# thermostat.net
KiCad netlist of a schematic drawn in EAGLE
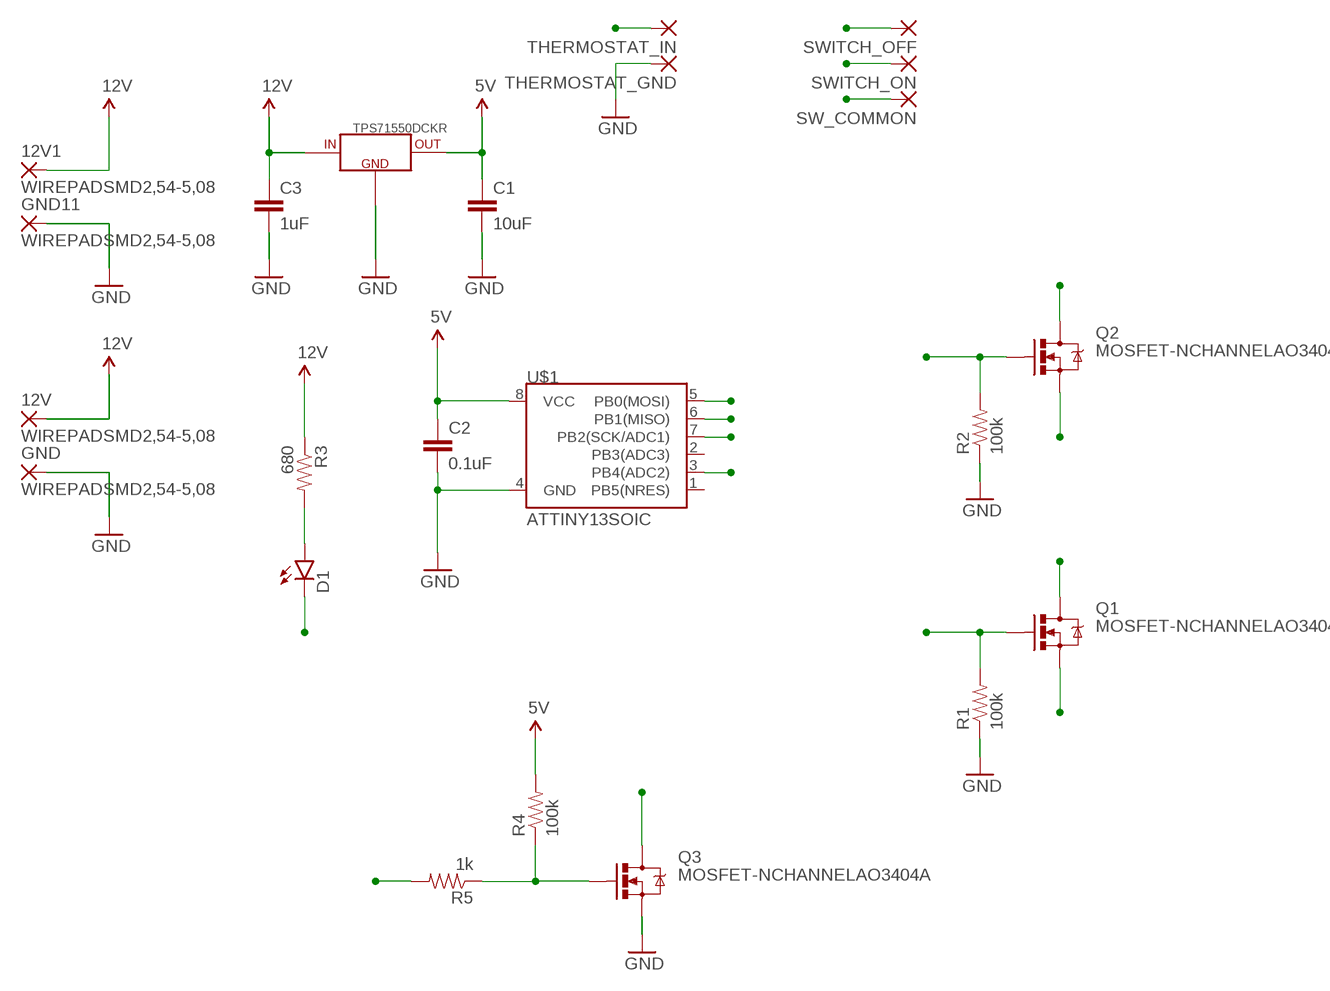
[diagram p0: schematic, sheet 1]

(export (version "E")
  (design (tool "Eeschema 10.0.6"))
  (components
    (comp (ref "12V")
      (value "WIREPADSMD2,54-5,08")
      (footprint "eagle-import:SMD2,54-5,08")
      (libsource (lib "eagle-import") (part "WIREPADSMD2,54-5,08"))
    )
    (comp (ref "12V1")
      (value "WIREPADSMD2,54-5,08")
      (footprint "eagle-import:SMD2,54-5,08")
      (libsource (lib "eagle-import") (part "WIREPADSMD2,54-5,08"))
    )
    (comp (ref "C1")
      (value "10uF")
      (footprint "eagle-import:1210")
      (libsource (lib "eagle-import") (part "CAP1210"))
    )
    (comp (ref "C2")
      (value "0.1uF")
      (footprint "eagle-import:0805")
      (libsource (lib "eagle-import") (part "CAP0805"))
    )
    (comp (ref "C3")
      (value "1uF")
      (footprint "eagle-import:1210")
      (libsource (lib "eagle-import") (part "CAP1210"))
    )
    (comp (ref "D1")
      (value "LED0603")
      (footprint "eagle-import:LED-0603")
      (libsource (lib "eagle-import") (part "LED0603"))
    )
    (comp (ref "GND")
      (value "WIREPADSMD2,54-5,08")
      (footprint "eagle-import:SMD2,54-5,08")
      (libsource (lib "eagle-import") (part "WIREPADSMD2,54-5,08"))
    )
    (comp (ref "GND11")
      (value "WIREPADSMD2,54-5,08")
      (footprint "eagle-import:SMD2,54-5,08")
      (libsource (lib "eagle-import") (part "WIREPADSMD2,54-5,08"))
    )
    (comp (ref "Q1")
      (value "MOSFET-NCHANNELAO3404A")
      (footprint "eagle-import:SOT23-3")
      (libsource (lib "eagle-import") (part "MOSFET-NCHANNELAO3404A"))
    )
    (comp (ref "Q2")
      (value "MOSFET-NCHANNELAO3404A")
      (footprint "eagle-import:SOT23-3")
      (libsource (lib "eagle-import") (part "MOSFET-NCHANNELAO3404A"))
    )
    (comp (ref "Q3")
      (value "MOSFET-NCHANNELAO3404A")
      (footprint "eagle-import:SOT23-3")
      (libsource (lib "eagle-import") (part "MOSFET-NCHANNELAO3404A"))
    )
    (comp (ref "R1")
      (value "100k")
      (footprint "eagle-import:0805")
      (libsource (lib "eagle-import") (part "RESISTOR0805-RES"))
    )
    (comp (ref "R2")
      (value "100k")
      (footprint "eagle-import:0805")
      (libsource (lib "eagle-import") (part "RESISTOR0805-RES"))
    )
    (comp (ref "R3")
      (value "680")
      (footprint "eagle-import:0805")
      (libsource (lib "eagle-import") (part "RESISTOR0805-RES"))
    )
    (comp (ref "R4")
      (value "100k")
      (footprint "eagle-import:0805")
      (libsource (lib "eagle-import") (part "RESISTOR0805-RES"))
    )
    (comp (ref "R5")
      (value "1k")
      (footprint "eagle-import:0805")
      (libsource (lib "eagle-import") (part "RESISTOR0805-RES"))
    )
    (comp (ref "SWITCH_OFF")
      (value "WIREPADSMD2,54-5,08")
      (footprint "eagle-import:SMD2,54-5,08")
      (libsource (lib "eagle-import") (part "WIREPADSMD2,54-5,08"))
    )
    (comp (ref "SWITCH_ON")
      (value "WIREPADSMD2,54-5,08")
      (footprint "eagle-import:SMD2,54-5,08")
      (libsource (lib "eagle-import") (part "WIREPADSMD2,54-5,08"))
    )
    (comp (ref "SW_COMMON")
      (value "WIREPADSMD2,54-5,08")
      (footprint "eagle-import:SMD2,54-5,08")
      (libsource (lib "eagle-import") (part "WIREPADSMD2,54-5,08"))
    )
    (comp (ref "THERMOSTAT_GND")
      (value "WIREPADSMD2,54-5,08")
      (footprint "eagle-import:SMD2,54-5,08")
      (libsource (lib "eagle-import") (part "WIREPADSMD2,54-5,08"))
    )
    (comp (ref "THERMOSTAT_IN")
      (value "WIREPADSMD2,54-5,08")
      (footprint "eagle-import:SMD2,54-5,08")
      (libsource (lib "eagle-import") (part "WIREPADSMD2,54-5,08"))
    )
    (comp (ref "TPS71550DCKR")
      (value "TPS715XX")
      (footprint "eagle-import:SC70-5")
      (libsource (lib "eagle-import") (part "TPS715XX"))
    )
    (comp (ref "U$1")
      (value "ATTINY13SOIC")
      (footprint "eagle-import:SO08")
      (libsource (lib "eagle-import") (part "ATTINY13SOIC"))
    )
  )
  (nets
    (net (code "1") (name "/HEAT_OFF") (class "Default")
      (node (ref "Q2") (pin "1") (pinfunction "G_1") (pintype "passive"))
      (node (ref "R2") (pin "2") (pinfunction "2_2") (pintype "passive"))
      (node (ref "U$1") (pin "5") (pinfunction "PB0(MOSI)_5") (pintype "bidirectional"))
    )
    (net (code "2") (name "/HEAT_ON") (class "Default")
      (node (ref "Q1") (pin "1") (pinfunction "G_1") (pintype "passive"))
      (node (ref "R1") (pin "2") (pinfunction "2_2") (pintype "passive"))
      (node (ref "U$1") (pin "6") (pinfunction "PB1(MISO)_6") (pintype "bidirectional"))
    )
    (net (code "3") (name "/LED") (class "Default")
      (node (ref "D1") (pin "C") (pinfunction "C_C") (pintype "passive"))
      (node (ref "U$1") (pin "3") (pinfunction "PB4(ADC2)_3") (pintype "bidirectional"))
    )
    (net (code "4") (name "/SENSOR_IN") (class "Default")
      (node (ref "Q3") (pin "3") (pinfunction "D_3") (pintype "passive"))
      (node (ref "U$1") (pin "7") (pinfunction "PB2(SCK/ADC1)_7") (pintype "bidirectional"))
    )
    (net (code "5") (name "/SWITCH_OFF") (class "Default")
      (node (ref "Q2") (pin "2") (pinfunction "S_2") (pintype "passive"))
      (node (ref "SWITCH_OFF") (pin "1") (pinfunction "P_1") (pintype "passive"))
    )
    (net (code "6") (name "/SWITCH_ON") (class "Default")
      (node (ref "Q1") (pin "2") (pinfunction "S_2") (pintype "passive"))
      (node (ref "SWITCH_ON") (pin "1") (pinfunction "P_1") (pintype "passive"))
    )
    (net (code "7") (name "/SW_COMMON") (class "Default")
      (node (ref "Q1") (pin "3") (pinfunction "D_3") (pintype "passive"))
      (node (ref "Q2") (pin "3") (pinfunction "D_3") (pintype "passive"))
      (node (ref "SW_COMMON") (pin "1") (pinfunction "P_1") (pintype "passive"))
    )
    (net (code "8") (name "/THERMOSTAT_IN") (class "Default")
      (node (ref "R5") (pin "2") (pinfunction "2_2") (pintype "passive"))
      (node (ref "THERMOSTAT_IN") (pin "1") (pinfunction "P_1") (pintype "passive"))
    )
    (net (code "9") (name "5V") (class "Default")
      (node (ref "C1") (pin "1") (pinfunction "1_1") (pintype "passive"))
      (node (ref "C2") (pin "1") (pinfunction "1_1") (pintype "passive"))
      (node (ref "R4") (pin "2") (pinfunction "2_2") (pintype "passive"))
      (node (ref "TPS71550DCKR") (pin "5") (pinfunction "OUT_5") (pintype "bidirectional"))
      (node (ref "U$1") (pin "8") (pinfunction "VCC_8") (pintype "bidirectional"))
    )
    (net (code "10") (name "12V") (class "Default")
      (node (ref "12V") (pin "1") (pinfunction "P_1") (pintype "passive"))
      (node (ref "12V1") (pin "1") (pinfunction "P_1") (pintype "passive"))
      (node (ref "C3") (pin "1") (pinfunction "1_1") (pintype "passive"))
      (node (ref "R3") (pin "1") (pinfunction "1_1") (pintype "passive"))
      (node (ref "TPS71550DCKR") (pin "4") (pinfunction "IN_4") (pintype "bidirectional"))
    )
    (net (code "11") (name "GND") (class "Default")
      (node (ref "C1") (pin "2") (pinfunction "2_2") (pintype "passive"))
      (node (ref "C2") (pin "2") (pinfunction "2_2") (pintype "passive"))
      (node (ref "C3") (pin "2") (pinfunction "2_2") (pintype "passive"))
      (node (ref "GND") (pin "1") (pinfunction "P_1") (pintype "passive"))
      (node (ref "GND11") (pin "1") (pinfunction "P_1") (pintype "passive"))
      (node (ref "Q3") (pin "2") (pinfunction "S_2") (pintype "passive"))
      (node (ref "R1") (pin "1") (pinfunction "1_1") (pintype "passive"))
      (node (ref "R2") (pin "1") (pinfunction "1_1") (pintype "passive"))
      (node (ref "THERMOSTAT_GND") (pin "1") (pinfunction "P_1") (pintype "passive"))
      (node (ref "TPS71550DCKR") (pin "2") (pinfunction "GND_2") (pintype "bidirectional"))
      (node (ref "U$1") (pin "4") (pinfunction "GND_4") (pintype "bidirectional"))
    )
    (net (code "12") (name "Net-(D1-PadA)") (class "Default")
      (node (ref "D1") (pin "A") (pinfunction "A_A") (pintype "passive"))
      (node (ref "R3") (pin "2") (pinfunction "2_2") (pintype "passive"))
    )
    (net (code "13") (name "Net-(Q3-G)") (class "Default")
      (node (ref "Q3") (pin "1") (pinfunction "G_1") (pintype "passive"))
      (node (ref "R4") (pin "1") (pinfunction "1_1") (pintype "passive"))
      (node (ref "R5") (pin "1") (pinfunction "1_1") (pintype "passive"))
    )
    (net (code "14") (name "unconnected-(U$1-PB3(ADC3)-Pad2)") (class "Default")
      (node (ref "U$1") (pin "2") (pinfunction "PB3(ADC3)_2") (pintype "bidirectional"))
    )
    (net (code "15") (name "unconnected-(U$1-PB5(NRES)-Pad1)") (class "Default")
      (node (ref "U$1") (pin "1") (pinfunction "PB5(NRES)_1") (pintype "bidirectional"))
    )
  )
)
